# Dispaly_LED.net
KiCad netlist of a schematic drawn in Altium Designer
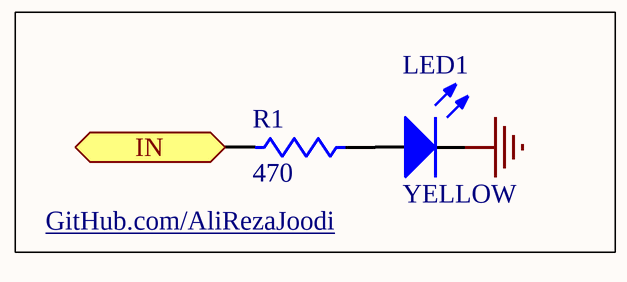
[diagram p0: Dispaly_LED.SchDoc]

(export (version "E")
  (design (tool "Eeschema 10.0.6"))
  (components
    (comp (ref "LED1")
      (value "YELLOW")
      (footprint "LED-5mm_Red")
      (description "Typical INFRARED GaAs LED")
      (fields (field (name "MANUFACTURER") "Generic Components") (field (name "PUBLISHER") "Altium Limited"))
      (libsource (lib "Miscellaneous Devices") (part "LED"))
    )
    (comp (ref "R1")
      (value "470")
      (footprint "AXIAL-0.4")
      (description "Resistor")
      (fields (field (name "MANUFACTURER") "Generic Components") (field (name "PUBLISHER") "Altium Limited"))
      (libsource (lib "Miscellaneous Devices") (part "Res1"))
    )
  )
  (nets
    (net (code "1") (name "/IN") (class "Default")
      (node (ref "R1") (pin "2") (pinfunction "2_2") (pintype "passive"))
    )
    (net (code "2") (name "GND") (class "Default")
      (node (ref "LED1") (pin "2") (pinfunction "K_2") (pintype "passive"))
    )
    (net (code "3") (name "Net-(LED1-A)") (class "Default")
      (node (ref "LED1") (pin "1") (pinfunction "A_1") (pintype "passive"))
      (node (ref "R1") (pin "1") (pinfunction "1_1") (pintype "passive"))
    )
  )
)
